# XMOS_power.net
KiCad netlist of a schematic drawn in Altium Designer
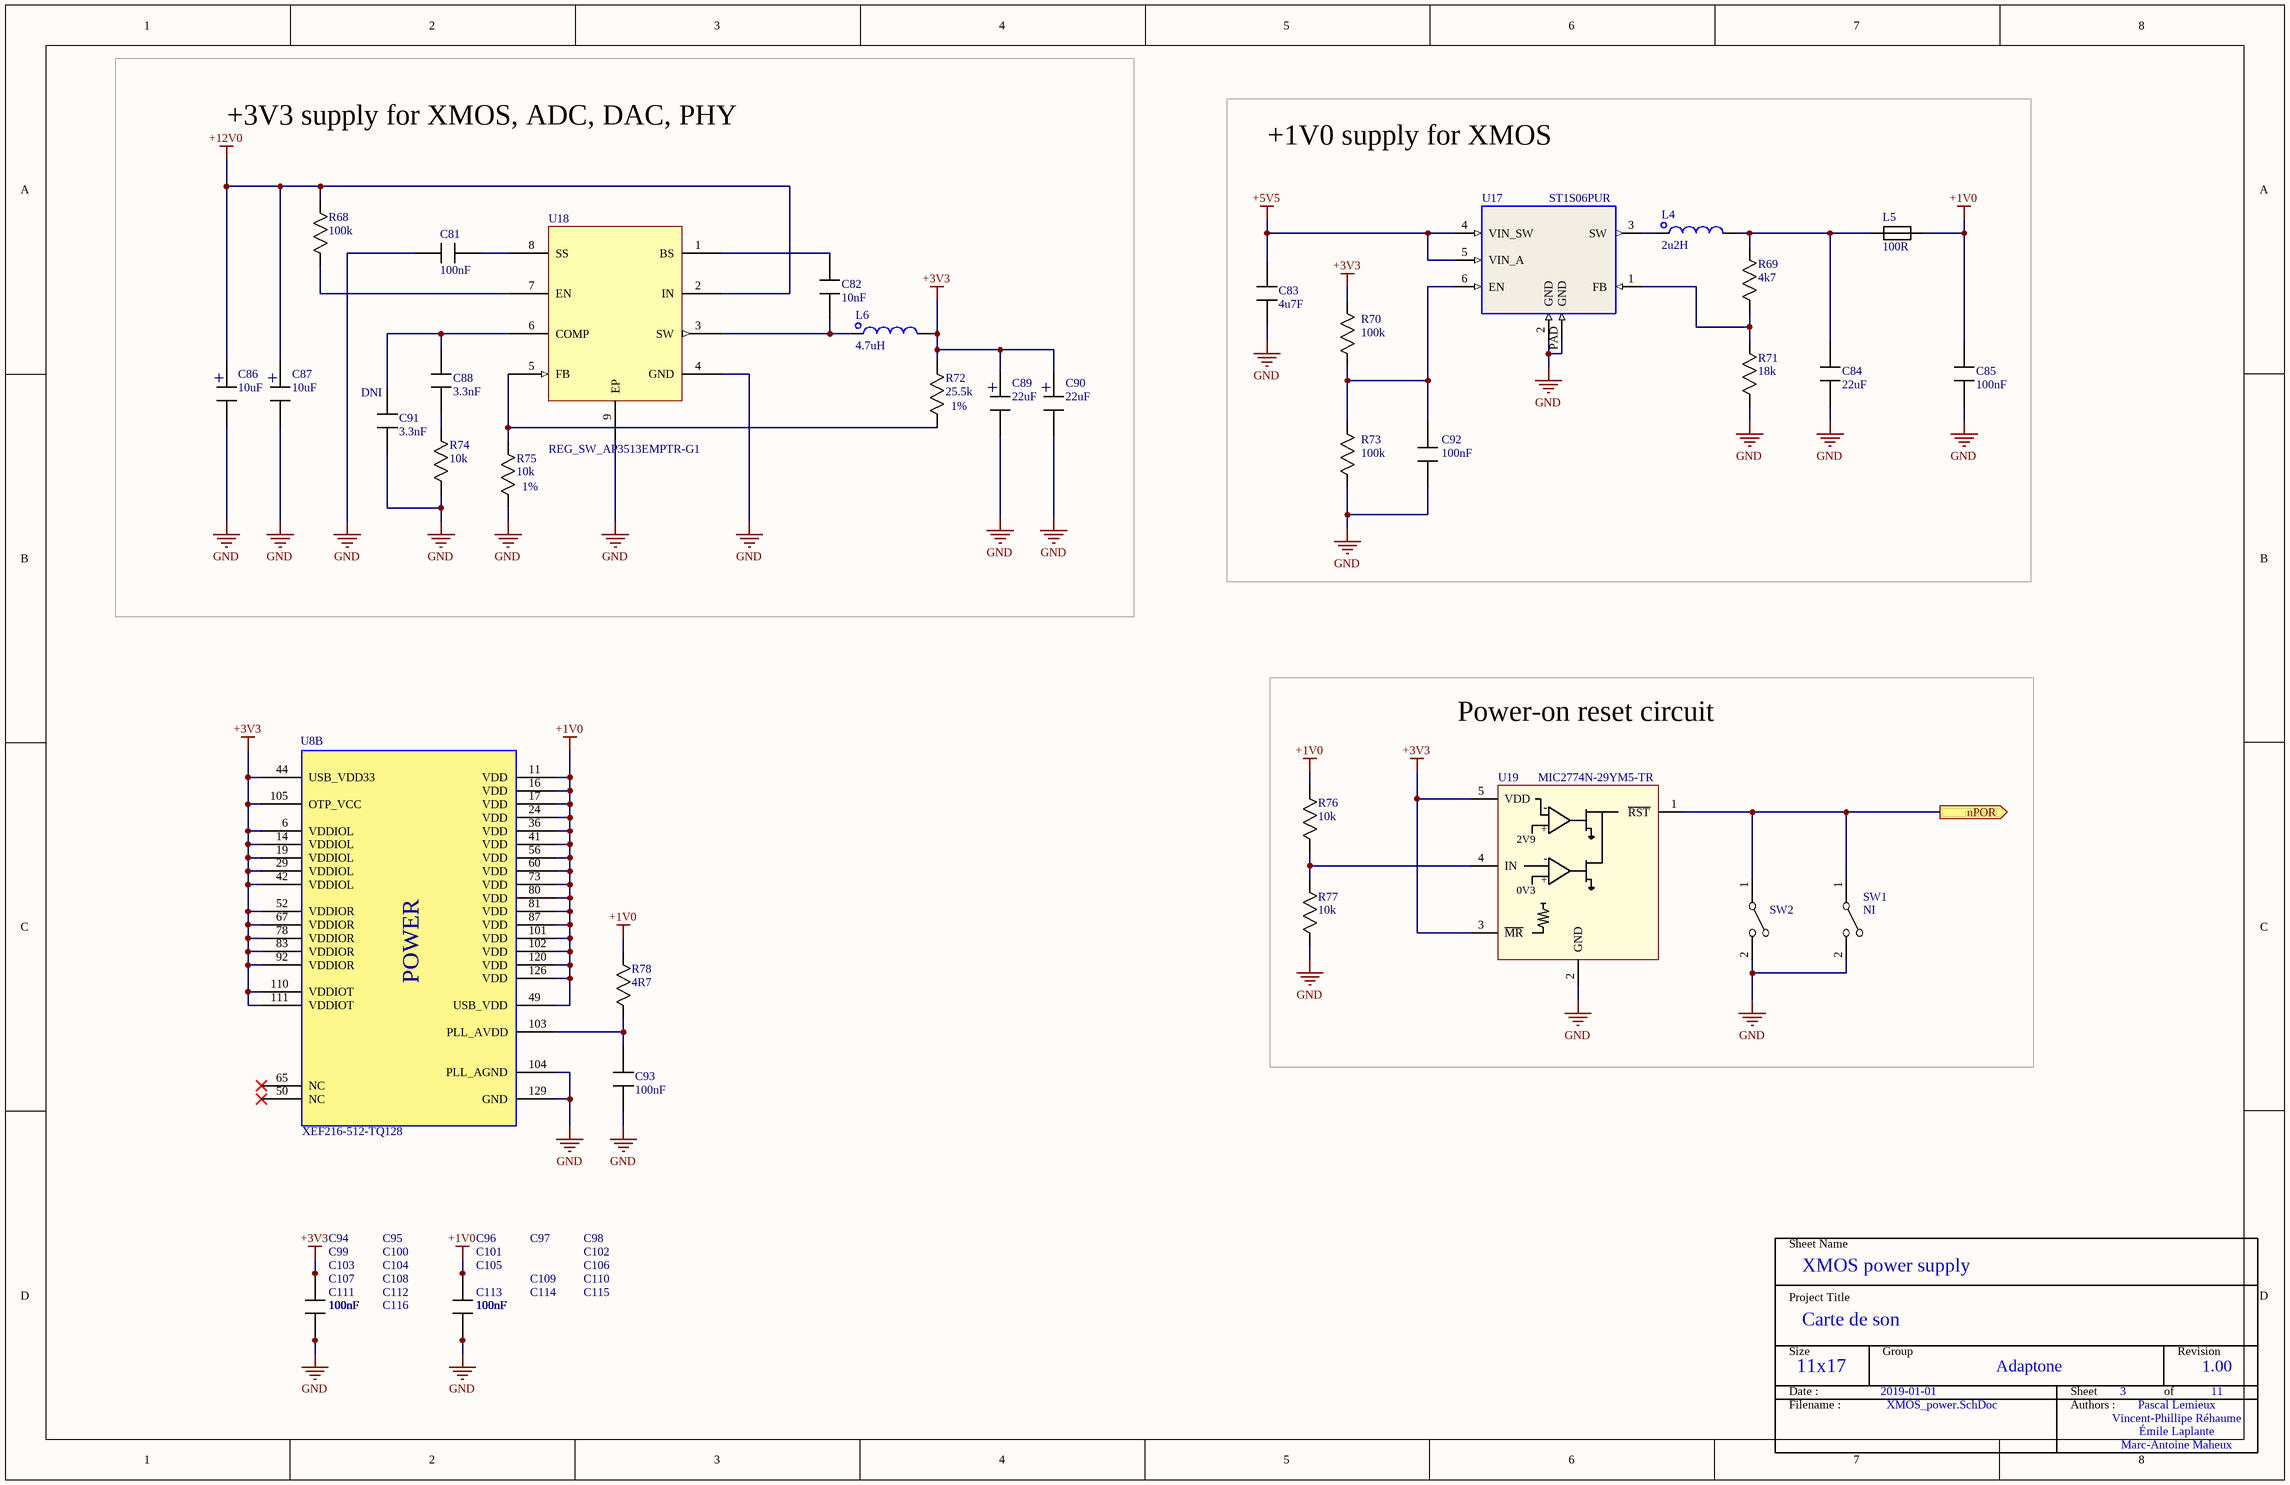
[diagram p0: XMOS_power.SchDoc]

(export (version "E")
  (design (tool "Eeschema 10.0.6"))
  (components
    (comp (ref "C81")
      (value "100nF")
      (footprint "0603")
      (description "Capacitor")
      (fields (field (name "MFG") "Samsung"))
      (libsource (lib "ADAPTONE_CARTE_DE_SON") (part "Capacitor"))
    )
    (comp (ref "C82")
      (value "10nF")
      (footprint "0603")
      (description "Capacitor")
      (fields (field (name "MFG") "Samsung"))
      (libsource (lib "ADAPTONE_CARTE_DE_SON") (part "Capacitor"))
    )
    (comp (ref "C83")
      (value "4u7F")
      (footprint "0805")
      (description "Capacitor")
      (fields (field (name "MFG") "Samsung"))
      (libsource (lib "ADAPTONE_CARTE_DE_SON") (part "Capacitor"))
    )
    (comp (ref "C84")
      (value "22uF")
      (footprint "1206")
      (description "Capacitor")
      (fields (field (name "MFG") "Samsung"))
      (libsource (lib "ADAPTONE_CARTE_DE_SON") (part "Capacitor"))
    )
    (comp (ref "C85")
      (value "100nF")
      (footprint "0603")
      (description "Capacitor")
      (fields (field (name "MFG") "Samsung"))
      (libsource (lib "ADAPTONE_CARTE_DE_SON") (part "Capacitor"))
    )
    (comp (ref "C86")
      (value "10uF")
      (footprint "CAP_RAD_SMD_DIA157")
      (description "Capacitor")
      (fields (field (name "MFG") "Nichicon") (field (name "Comment") "Capacitor_Polarized"))
      (libsource (lib "ADAPTONE_CARTE_DE_SON") (part "Capacitor_Polarized"))
    )
    (comp (ref "C87")
      (value "10uF")
      (footprint "CAP_RAD_SMD_DIA157")
      (description "Capacitor")
      (fields (field (name "MFG") "Nichicon") (field (name "Comment") "Capacitor_Polarized"))
      (libsource (lib "ADAPTONE_CARTE_DE_SON") (part "Capacitor_Polarized"))
    )
    (comp (ref "C88")
      (value "3.3nF")
      (footprint "0603")
      (description "Capacitor")
      (fields (field (name "MFG") "Samsung"))
      (libsource (lib "ADAPTONE_CARTE_DE_SON") (part "Capacitor"))
    )
    (comp (ref "C89")
      (value "22uF")
      (footprint "CAP_RAD_SMD_DIA157")
      (description "Capacitor")
      (fields (field (name "MFG") "Nichicon") (field (name "Comment") "Capacitor_Polarized"))
      (libsource (lib "ADAPTONE_CARTE_DE_SON") (part "Capacitor_Polarized"))
    )
    (comp (ref "C90")
      (value "22uF")
      (footprint "CAP_RAD_SMD_DIA157")
      (description "Capacitor")
      (fields (field (name "MFG") "Nichicon") (field (name "Comment") "Capacitor_Polarized"))
      (libsource (lib "ADAPTONE_CARTE_DE_SON") (part "Capacitor_Polarized"))
    )
    (comp (ref "C91")
      (value "3.3nF")
      (footprint "0603")
      (description "Capacitor")
      (fields (field (name "MFG") "Samsung") (field (name "NOTE") "DNI"))
      (libsource (lib "ADAPTONE_CARTE_DE_SON") (part "Capacitor"))
    )
    (comp (ref "C92")
      (value "100nF")
      (footprint "0603")
      (description "Capacitor")
      (fields (field (name "MFG") "Samsung"))
      (libsource (lib "ADAPTONE_CARTE_DE_SON") (part "Capacitor"))
    )
    (comp (ref "C93")
      (value "100nF")
      (footprint "0603")
      (description "Capacitor")
      (fields (field (name "MFG") "Samsung"))
      (libsource (lib "ADAPTONE_CARTE_DE_SON") (part "Capacitor"))
    )
    (comp (ref "C94")
      (value "100nF")
      (footprint "0603")
      (description "Capacitor")
      (fields (field (name "MFG") "Samsung"))
      (libsource (lib "ADAPTONE_CARTE_DE_SON") (part "Capacitor"))
    )
    (comp (ref "C95")
      (value "100nF")
      (footprint "0603")
      (description "Capacitor")
      (fields (field (name "MFG") "Samsung"))
      (libsource (lib "ADAPTONE_CARTE_DE_SON") (part "Capacitor"))
    )
    (comp (ref "C96")
      (value "100nF")
      (footprint "0603")
      (description "Capacitor")
      (fields (field (name "MFG") "Samsung"))
      (libsource (lib "ADAPTONE_CARTE_DE_SON") (part "Capacitor"))
    )
    (comp (ref "C97")
      (value "100nF")
      (footprint "0603")
      (description "Capacitor")
      (fields (field (name "MFG") "Samsung"))
      (libsource (lib "ADAPTONE_CARTE_DE_SON") (part "Capacitor"))
    )
    (comp (ref "C98")
      (value "100nF")
      (footprint "0603")
      (description "Capacitor")
      (fields (field (name "MFG") "Samsung"))
      (libsource (lib "ADAPTONE_CARTE_DE_SON") (part "Capacitor"))
    )
    (comp (ref "C99")
      (value "100nF")
      (footprint "0603")
      (description "Capacitor")
      (fields (field (name "MFG") "Samsung"))
      (libsource (lib "ADAPTONE_CARTE_DE_SON") (part "Capacitor"))
    )
    (comp (ref "C100")
      (value "100nF")
      (footprint "0603")
      (description "Capacitor")
      (fields (field (name "MFG") "Samsung"))
      (libsource (lib "ADAPTONE_CARTE_DE_SON") (part "Capacitor"))
    )
    (comp (ref "C101")
      (value "100nF")
      (footprint "0603")
      (description "Capacitor")
      (fields (field (name "MFG") "Samsung"))
      (libsource (lib "ADAPTONE_CARTE_DE_SON") (part "Capacitor"))
    )
    (comp (ref "C102")
      (value "100nF")
      (footprint "0603")
      (description "Capacitor")
      (fields (field (name "MFG") "Samsung"))
      (libsource (lib "ADAPTONE_CARTE_DE_SON") (part "Capacitor"))
    )
    (comp (ref "C103")
      (value "100nF")
      (footprint "0603")
      (description "Capacitor")
      (fields (field (name "MFG") "Samsung"))
      (libsource (lib "ADAPTONE_CARTE_DE_SON") (part "Capacitor"))
    )
    (comp (ref "C104")
      (value "100nF")
      (footprint "0603")
      (description "Capacitor")
      (fields (field (name "MFG") "Samsung"))
      (libsource (lib "ADAPTONE_CARTE_DE_SON") (part "Capacitor"))
    )
    (comp (ref "C105")
      (value "100nF")
      (footprint "0603")
      (description "Capacitor")
      (fields (field (name "MFG") "Samsung"))
      (libsource (lib "ADAPTONE_CARTE_DE_SON") (part "Capacitor"))
    )
    (comp (ref "C106")
      (value "100nF")
      (footprint "0603")
      (description "Capacitor")
      (fields (field (name "MFG") "Samsung"))
      (libsource (lib "ADAPTONE_CARTE_DE_SON") (part "Capacitor"))
    )
    (comp (ref "C107")
      (value "100nF")
      (footprint "0603")
      (description "Capacitor")
      (fields (field (name "MFG") "Samsung"))
      (libsource (lib "ADAPTONE_CARTE_DE_SON") (part "Capacitor"))
    )
    (comp (ref "C108")
      (value "100nF")
      (footprint "0603")
      (description "Capacitor")
      (fields (field (name "MFG") "Samsung"))
      (libsource (lib "ADAPTONE_CARTE_DE_SON") (part "Capacitor"))
    )
    (comp (ref "C109")
      (value "100nF")
      (footprint "0603")
      (description "Capacitor")
      (fields (field (name "MFG") "Samsung"))
      (libsource (lib "ADAPTONE_CARTE_DE_SON") (part "Capacitor"))
    )
    (comp (ref "C110")
      (value "100nF")
      (footprint "0603")
      (description "Capacitor")
      (fields (field (name "MFG") "Samsung"))
      (libsource (lib "ADAPTONE_CARTE_DE_SON") (part "Capacitor"))
    )
    (comp (ref "C111")
      (value "100nF")
      (footprint "0603")
      (description "Capacitor")
      (fields (field (name "MFG") "Samsung"))
      (libsource (lib "ADAPTONE_CARTE_DE_SON") (part "Capacitor"))
    )
    (comp (ref "C112")
      (value "100nF")
      (footprint "0603")
      (description "Capacitor")
      (fields (field (name "MFG") "Samsung"))
      (libsource (lib "ADAPTONE_CARTE_DE_SON") (part "Capacitor"))
    )
    (comp (ref "C113")
      (value "100nF")
      (footprint "0603")
      (description "Capacitor")
      (fields (field (name "MFG") "Samsung"))
      (libsource (lib "ADAPTONE_CARTE_DE_SON") (part "Capacitor"))
    )
    (comp (ref "C114")
      (value "100nF")
      (footprint "0603")
      (description "Capacitor")
      (fields (field (name "MFG") "Samsung"))
      (libsource (lib "ADAPTONE_CARTE_DE_SON") (part "Capacitor"))
    )
    (comp (ref "C115")
      (value "100nF")
      (footprint "0603")
      (description "Capacitor")
      (fields (field (name "MFG") "Samsung"))
      (libsource (lib "ADAPTONE_CARTE_DE_SON") (part "Capacitor"))
    )
    (comp (ref "C116")
      (value "100nF")
      (footprint "0603")
      (description "Capacitor")
      (fields (field (name "MFG") "Samsung"))
      (libsource (lib "ADAPTONE_CARTE_DE_SON") (part "Capacitor"))
    )
    (comp (ref "L4")
      (value "2u2H")
      (footprint "IND_252012CDMC/DS")
      (description "Inductor")
      (fields (field (name "MFG") "Murata"))
      (libsource (lib "ADAPTONE_CARTE_DE_SON") (part "Inductor"))
    )
    (comp (ref "L5")
      (value "100R")
      (footprint "0805")
      (description "Ferrite")
      (fields (field (name "MFG") "Bourns"))
      (libsource (lib "ADAPTONE_CARTE_DE_SON") (part "Ferrite"))
    )
    (comp (ref "L6")
      (value "4.7uH")
      (footprint "SRN5040-4R7M")
      (description "Inductor")
      (fields (field (name "MFG") "Bourns Inc."))
      (libsource (lib "ADAPTONE_CARTE_DE_SON") (part "Inductor"))
    )
    (comp (ref "R68")
      (value "100k")
      (footprint "0603")
      (description "Resistor")
      (fields (field (name "MFG") "Stackpole Electronics Inc"))
      (libsource (lib "ADAPTONE_CARTE_DE_SON") (part "Resistor"))
    )
    (comp (ref "R69")
      (value "4k7")
      (footprint "0603")
      (description "Resistor")
      (fields (field (name "MFG") "Yageo"))
      (libsource (lib "ADAPTONE_CARTE_DE_SON") (part "Resistor"))
    )
    (comp (ref "R70")
      (value "100k")
      (footprint "0603")
      (description "Resistor")
      (fields (field (name "MFG") "Yageo"))
      (libsource (lib "ADAPTONE_CARTE_DE_SON") (part "Resistor"))
    )
    (comp (ref "R71")
      (value "18k")
      (footprint "0603")
      (description "Resistor")
      (fields (field (name "MFG") "Yageo"))
      (libsource (lib "ADAPTONE_CARTE_DE_SON") (part "Resistor"))
    )
    (comp (ref "R72")
      (value "25.5k")
      (footprint "0603")
      (description "Resistor")
      (fields (field (name "MFG") "Stackpole Electronics Inc") (field (name "TOLERANCE") "1%"))
      (libsource (lib "ADAPTONE_CARTE_DE_SON") (part "Resistor"))
    )
    (comp (ref "R73")
      (value "100k")
      (footprint "0603")
      (description "Resistor")
      (fields (field (name "MFG") "Yageo"))
      (libsource (lib "ADAPTONE_CARTE_DE_SON") (part "Resistor"))
    )
    (comp (ref "R74")
      (value "10k")
      (footprint "0603")
      (description "Resistor")
      (fields (field (name "MFG") "Yageo"))
      (libsource (lib "ADAPTONE_CARTE_DE_SON") (part "Resistor"))
    )
    (comp (ref "R75")
      (value "10k")
      (footprint "0603")
      (description "Resistor")
      (fields (field (name "MFG") "Stackpole Electronics Inc") (field (name "TOLERANCE") "1%"))
      (libsource (lib "ADAPTONE_CARTE_DE_SON") (part "Resistor"))
    )
    (comp (ref "R76")
      (value "10k")
      (footprint "0603")
      (description "Resistor")
      (fields (field (name "MFG") "Yageo"))
      (libsource (lib "ADAPTONE_CARTE_DE_SON") (part "Resistor"))
    )
    (comp (ref "R77")
      (value "10k")
      (footprint "0603")
      (description "Resistor")
      (fields (field (name "MFG") "Yageo"))
      (libsource (lib "ADAPTONE_CARTE_DE_SON") (part "Resistor"))
    )
    (comp (ref "R78")
      (value "4R7")
      (footprint "0603")
      (description "Resistor")
      (fields (field (name "MFG") "Yageo"))
      (libsource (lib "ADAPTONE_CARTE_DE_SON") (part "Resistor"))
    )
    (comp (ref "SW1")
      (value "Button")
      (footprint "BUTTON_WS-TASV")
      (fields (field (name "MFG") "Wurth") (field (name "NI") "NI"))
      (libsource (lib "ADAPTONE_CARTE_DE_SON") (part "Button"))
    )
    (comp (ref "SW2")
      (value "Button")
      (footprint "BUTTON_WS-TASV")
      (fields (field (name "MFG") "Wurth"))
      (libsource (lib "ADAPTONE_CARTE_DE_SON") (part "Button"))
    )
    (comp (ref "U8")
      (value "~")
      (footprint "TQFP128_XMOS")
      (description "32-bit multicore microcontroller. 2 Tiles. 16 Logical Cores. 512KB SRAM. 1000MIPS. TQFP128.")
      (fields (field (name "MFG") "XMOS") (field (name "MFG_PN") "XEF216-512-TQ128"))
      (libsource (lib "ADAPTONE_CARTE_DE_SON") (part "XMOS_XEF216-512-TQ128"))
    )
    (comp (ref "U17")
      (value "ST1S06PUR")
      (footprint "DFN6_ST1S06")
      (description "DC-DC Buck Converter, 1.5A, 1.5MHz, DFN6")
      (fields (field (name "MFG") "ST Microelectronics") (field (name "MFG_PN") "ST1S06PUR"))
      (libsource (lib "ADAPTONE_CARTE_DE_SON") (part "ST1S06PUR"))
    )
    (comp (ref "U18")
      (value "REG_SW_AP3513EMPTR-G1")
      (footprint "AP3513EMPTR-G1")
      (fields
        (field (name "MFG") "Diodes Incorporated")
        (field (name "MFG PART NUMBER") "AP3513EMPTR-G1")
        (field (name "CREATEDBY") "Emile Laplante")
        (field (name "VERIFIEDBY") "*")
      )
      (libsource (lib "LIB_ADAPTONE_EMILE_LAPLANTE") (part "REG_SW_AP3513EMPTR-G1"))
    )
    (comp (ref "U19")
      (value "MIC2774N-29YM5-TR")
      (footprint "SOT23_5")
      (description "Voltage supervisor and power-on timer, dual")
      (fields (field (name "MFG") "Micrel"))
      (libsource (lib "ADAPTONE_CARTE_DE_SON") (part "MIC2774N-29YM5-TR"))
    )
  )
  (nets
    (net (code "1") (name "+1V0") (class "Default")
      (node (ref "C101") (pin "1") (pintype "passive"))
      (node (ref "C102") (pin "1") (pintype "passive"))
      (node (ref "C105") (pin "1") (pintype "passive"))
      (node (ref "C106") (pin "1") (pintype "passive"))
      (node (ref "C109") (pin "1") (pintype "passive"))
      (node (ref "C110") (pin "1") (pintype "passive"))
      (node (ref "C113") (pin "1") (pintype "passive"))
      (node (ref "C114") (pin "1") (pintype "passive"))
      (node (ref "C115") (pin "1") (pintype "passive"))
      (node (ref "C85") (pin "1") (pintype "passive"))
      (node (ref "C96") (pin "1") (pintype "passive"))
      (node (ref "C97") (pin "1") (pintype "passive"))
      (node (ref "C98") (pin "1") (pintype "passive"))
      (node (ref "L5") (pin "2") (pintype "passive"))
      (node (ref "R76") (pin "1") (pintype "passive"))
      (node (ref "R78") (pin "1") (pintype "passive"))
      (node (ref "U8") (pin "101") (pinfunction "VDD_101") (pintype "power_in"))
      (node (ref "U8") (pin "102") (pinfunction "VDD_102") (pintype "power_in"))
      (node (ref "U8") (pin "11") (pinfunction "VDD_11") (pintype "power_in"))
      (node (ref "U8") (pin "120") (pinfunction "VDD_120") (pintype "power_in"))
      (node (ref "U8") (pin "126") (pinfunction "VDD_126") (pintype "power_in"))
      (node (ref "U8") (pin "16") (pinfunction "VDD_16") (pintype "power_in"))
      (node (ref "U8") (pin "17") (pinfunction "VDD_17") (pintype "power_in"))
      (node (ref "U8") (pin "24") (pinfunction "VDD_24") (pintype "power_in"))
      (node (ref "U8") (pin "36") (pinfunction "VDD_36") (pintype "power_in"))
      (node (ref "U8") (pin "41") (pinfunction "VDD_41") (pintype "power_in"))
      (node (ref "U8") (pin "49") (pinfunction "USB_VDD_49") (pintype "power_in"))
      (node (ref "U8") (pin "56") (pinfunction "VDD_56") (pintype "power_in"))
      (node (ref "U8") (pin "60") (pinfunction "VDD_60") (pintype "power_in"))
      (node (ref "U8") (pin "73") (pinfunction "VDD_73") (pintype "power_in"))
      (node (ref "U8") (pin "80") (pinfunction "VDD_80") (pintype "power_in"))
      (node (ref "U8") (pin "81") (pinfunction "VDD_81") (pintype "power_in"))
      (node (ref "U8") (pin "87") (pinfunction "VDD_87") (pintype "power_in"))
    )
    (net (code "2") (name "+3V3") (class "Default")
      (node (ref "C100") (pin "1") (pintype "passive"))
      (node (ref "C103") (pin "1") (pintype "passive"))
      (node (ref "C104") (pin "1") (pintype "passive"))
      (node (ref "C107") (pin "1") (pintype "passive"))
      (node (ref "C108") (pin "1") (pintype "passive"))
      (node (ref "C111") (pin "1") (pintype "passive"))
      (node (ref "C112") (pin "1") (pintype "passive"))
      (node (ref "C116") (pin "1") (pintype "passive"))
      (node (ref "C89") (pin "+") (pintype "passive"))
      (node (ref "C90") (pin "+") (pintype "passive"))
      (node (ref "C94") (pin "1") (pintype "passive"))
      (node (ref "C95") (pin "1") (pintype "passive"))
      (node (ref "C99") (pin "1") (pintype "passive"))
      (node (ref "L6") (pin "2") (pintype "passive"))
      (node (ref "R70") (pin "1") (pintype "passive"))
      (node (ref "R72") (pin "1") (pintype "passive"))
      (node (ref "U19") (pin "3") (pinfunction "~{MR}_3") (pintype "passive"))
      (node (ref "U19") (pin "5") (pinfunction "VDD_5") (pintype "passive"))
      (node (ref "U8") (pin "105") (pinfunction "OTP_VCC_105") (pintype "power_in"))
      (node (ref "U8") (pin "110") (pinfunction "VDDIOT_110") (pintype "power_in"))
      (node (ref "U8") (pin "111") (pinfunction "VDDIOT_111") (pintype "power_in"))
      (node (ref "U8") (pin "14") (pinfunction "VDDIOL_14") (pintype "power_in"))
      (node (ref "U8") (pin "19") (pinfunction "VDDIOL_19") (pintype "power_in"))
      (node (ref "U8") (pin "29") (pinfunction "VDDIOL_29") (pintype "power_in"))
      (node (ref "U8") (pin "42") (pinfunction "VDDIOL_42") (pintype "power_in"))
      (node (ref "U8") (pin "44") (pinfunction "USB_VDD33_44") (pintype "power_in"))
      (node (ref "U8") (pin "52") (pinfunction "VDDIOR_52") (pintype "power_in"))
      (node (ref "U8") (pin "6") (pinfunction "VDDIOL_6") (pintype "power_in"))
      (node (ref "U8") (pin "67") (pinfunction "VDDIOR_67") (pintype "power_in"))
      (node (ref "U8") (pin "78") (pinfunction "VDDIOR_78") (pintype "power_in"))
      (node (ref "U8") (pin "83") (pinfunction "VDDIOR_83") (pintype "power_in"))
      (node (ref "U8") (pin "92") (pinfunction "VDDIOR_92") (pintype "power_in"))
    )
    (net (code "3") (name "+5V5") (class "Default")
      (node (ref "C83") (pin "1") (pintype "passive"))
      (node (ref "U17") (pin "4") (pinfunction "VIN_SW_4") (pintype "input"))
      (node (ref "U17") (pin "5") (pinfunction "VIN_A_5") (pintype "input"))
    )
    (net (code "4") (name "+12V0") (class "Default")
      (node (ref "C86") (pin "+") (pintype "passive"))
      (node (ref "C87") (pin "+") (pintype "passive"))
      (node (ref "R68") (pin "2") (pintype "passive"))
      (node (ref "U18") (pin "2") (pinfunction "IN_2") (pintype "power_in"))
    )
    (net (code "5") (name "/nPOR") (class "Default")
      (node (ref "SW1") (pin "1") (pintype "passive"))
      (node (ref "SW2") (pin "1") (pintype "passive"))
      (node (ref "U19") (pin "1") (pinfunction "~{RST}_1") (pintype "open_collector"))
    )
    (net (code "6") (name "GND") (class "Default")
      (node (ref "C100") (pin "2") (pintype "passive"))
      (node (ref "C101") (pin "2") (pintype "passive"))
      (node (ref "C102") (pin "2") (pintype "passive"))
      (node (ref "C103") (pin "2") (pintype "passive"))
      (node (ref "C104") (pin "2") (pintype "passive"))
      (node (ref "C105") (pin "2") (pintype "passive"))
      (node (ref "C106") (pin "2") (pintype "passive"))
      (node (ref "C107") (pin "2") (pintype "passive"))
      (node (ref "C108") (pin "2") (pintype "passive"))
      (node (ref "C109") (pin "2") (pintype "passive"))
      (node (ref "C110") (pin "2") (pintype "passive"))
      (node (ref "C111") (pin "2") (pintype "passive"))
      (node (ref "C112") (pin "2") (pintype "passive"))
      (node (ref "C113") (pin "2") (pintype "passive"))
      (node (ref "C114") (pin "2") (pintype "passive"))
      (node (ref "C115") (pin "2") (pintype "passive"))
      (node (ref "C116") (pin "2") (pintype "passive"))
      (node (ref "C81") (pin "1") (pintype "passive"))
      (node (ref "C83") (pin "2") (pintype "passive"))
      (node (ref "C84") (pin "2") (pintype "passive"))
      (node (ref "C85") (pin "2") (pintype "passive"))
      (node (ref "C86") (pin "-") (pintype "passive"))
      (node (ref "C87") (pin "-") (pintype "passive"))
      (node (ref "C89") (pin "-") (pintype "passive"))
      (node (ref "C90") (pin "-") (pintype "passive"))
      (node (ref "C91") (pin "2") (pintype "passive"))
      (node (ref "C92") (pin "2") (pintype "passive"))
      (node (ref "C93") (pin "2") (pintype "passive"))
      (node (ref "C94") (pin "2") (pintype "passive"))
      (node (ref "C95") (pin "2") (pintype "passive"))
      (node (ref "C96") (pin "2") (pintype "passive"))
      (node (ref "C97") (pin "2") (pintype "passive"))
      (node (ref "C98") (pin "2") (pintype "passive"))
      (node (ref "C99") (pin "2") (pintype "passive"))
      (node (ref "R71") (pin "2") (pintype "passive"))
      (node (ref "R73") (pin "2") (pintype "passive"))
      (node (ref "R74") (pin "2") (pintype "passive"))
      (node (ref "R75") (pin "2") (pintype "passive"))
      (node (ref "R77") (pin "2") (pintype "passive"))
      (node (ref "SW1") (pin "2") (pintype "passive"))
      (node (ref "SW2") (pin "2") (pintype "passive"))
      (node (ref "U17") (pin "2") (pinfunction "GND_2") (pintype "input"))
      (node (ref "U17") (pin "PAD") (pinfunction "GND_PAD") (pintype "input"))
      (node (ref "U18") (pin "4") (pinfunction "GND_4") (pintype "passive"))
      (node (ref "U18") (pin "9") (pinfunction "EP_9") (pintype "passive"))
      (node (ref "U19") (pin "2") (pinfunction "GND_2") (pintype "passive"))
      (node (ref "U8") (pin "104") (pinfunction "PLL_AGND_104") (pintype "power_in"))
      (node (ref "U8") (pin "129") (pinfunction "GND_129") (pintype "power_in"))
    )
    (net (code "7") (name "Net-(C84-Pad1)") (class "Default")
      (node (ref "C84") (pin "1") (pintype "passive"))
      (node (ref "L4") (pin "2") (pintype "passive"))
      (node (ref "L5") (pin "1") (pintype "passive"))
      (node (ref "R69") (pin "1") (pintype "passive"))
    )
    (net (code "8") (name "Net-(C88-Pad2)") (class "Default")
      (node (ref "C88") (pin "2") (pintype "passive"))
      (node (ref "R74") (pin "1") (pintype "passive"))
    )
    (net (code "9") (name "Net-(U8B-PLL_AVDD)") (class "Default")
      (node (ref "C93") (pin "1") (pintype "passive"))
      (node (ref "R78") (pin "2") (pintype "passive"))
      (node (ref "U8") (pin "103") (pinfunction "PLL_AVDD_103") (pintype "power_in"))
    )
    (net (code "10") (name "Net-(U17-EN)") (class "Default")
      (node (ref "C92") (pin "1") (pintype "passive"))
      (node (ref "R70") (pin "2") (pintype "passive"))
      (node (ref "R73") (pin "1") (pintype "passive"))
      (node (ref "U17") (pin "6") (pinfunction "EN_6") (pintype "input"))
    )
    (net (code "11") (name "Net-(U17-FB)") (class "Default")
      (node (ref "R69") (pin "2") (pintype "passive"))
      (node (ref "R71") (pin "1") (pintype "passive"))
      (node (ref "U17") (pin "1") (pinfunction "FB_1") (pintype "input"))
    )
    (net (code "12") (name "Net-(U17-SW)") (class "Default")
      (node (ref "L4") (pin "1") (pintype "passive"))
      (node (ref "U17") (pin "3") (pinfunction "SW_3") (pintype "output"))
    )
    (net (code "13") (name "Net-(U18-BS)") (class "Default")
      (node (ref "C82") (pin "1") (pintype "passive"))
      (node (ref "U18") (pin "1") (pinfunction "BS_1") (pintype "passive"))
    )
    (net (code "14") (name "Net-(U18-COMP)") (class "Default")
      (node (ref "C88") (pin "1") (pintype "passive"))
      (node (ref "C91") (pin "1") (pintype "passive"))
      (node (ref "U18") (pin "6") (pinfunction "COMP_6") (pintype "passive"))
    )
    (net (code "15") (name "Net-(U18-EN)") (class "Default")
      (node (ref "R68") (pin "1") (pintype "passive"))
      (node (ref "U18") (pin "7") (pinfunction "EN_7") (pintype "passive"))
    )
    (net (code "16") (name "Net-(U18-FB)") (class "Default")
      (node (ref "R72") (pin "2") (pintype "passive"))
      (node (ref "R75") (pin "1") (pintype "passive"))
      (node (ref "U18") (pin "5") (pinfunction "FB_5") (pintype "input"))
    )
    (net (code "17") (name "Net-(U18-SS)") (class "Default")
      (node (ref "C81") (pin "2") (pintype "passive"))
      (node (ref "U18") (pin "8") (pinfunction "SS_8") (pintype "passive"))
    )
    (net (code "18") (name "Net-(U18-SW)") (class "Default")
      (node (ref "C82") (pin "2") (pintype "passive"))
      (node (ref "L6") (pin "1") (pintype "passive"))
      (node (ref "U18") (pin "3") (pinfunction "SW_3") (pintype "output"))
    )
    (net (code "19") (name "Net-(U19-IN)") (class "Default")
      (node (ref "R76") (pin "2") (pintype "passive"))
      (node (ref "R77") (pin "1") (pintype "passive"))
      (node (ref "U19") (pin "4") (pinfunction "IN_4") (pintype "passive"))
    )
    (net (code "20") (name "unconnected-(SW1-Pad3)") (class "Default")
      (node (ref "SW1") (pin "3") (pintype "passive"))
    )
    (net (code "21") (name "unconnected-(SW1-Pad4)") (class "Default")
      (node (ref "SW1") (pin "4") (pintype "passive"))
    )
    (net (code "22") (name "unconnected-(SW2-Pad3)") (class "Default")
      (node (ref "SW2") (pin "3") (pintype "passive"))
    )
    (net (code "23") (name "unconnected-(SW2-Pad4)") (class "Default")
      (node (ref "SW2") (pin "4") (pintype "passive"))
    )
    (net (code "24") (name "unconnected-(U8B-NC-Pad50)") (class "Default")
      (node (ref "U8") (pin "50") (pinfunction "NC_50") (pintype "passive+no_connect"))
    )
    (net (code "25") (name "unconnected-(U8B-NC-Pad65)") (class "Default")
      (node (ref "U8") (pin "65") (pinfunction "NC_65") (pintype "passive+no_connect"))
    )
  )
)
